# IN.net
KiCad netlist of a schematic drawn in Altium Designer
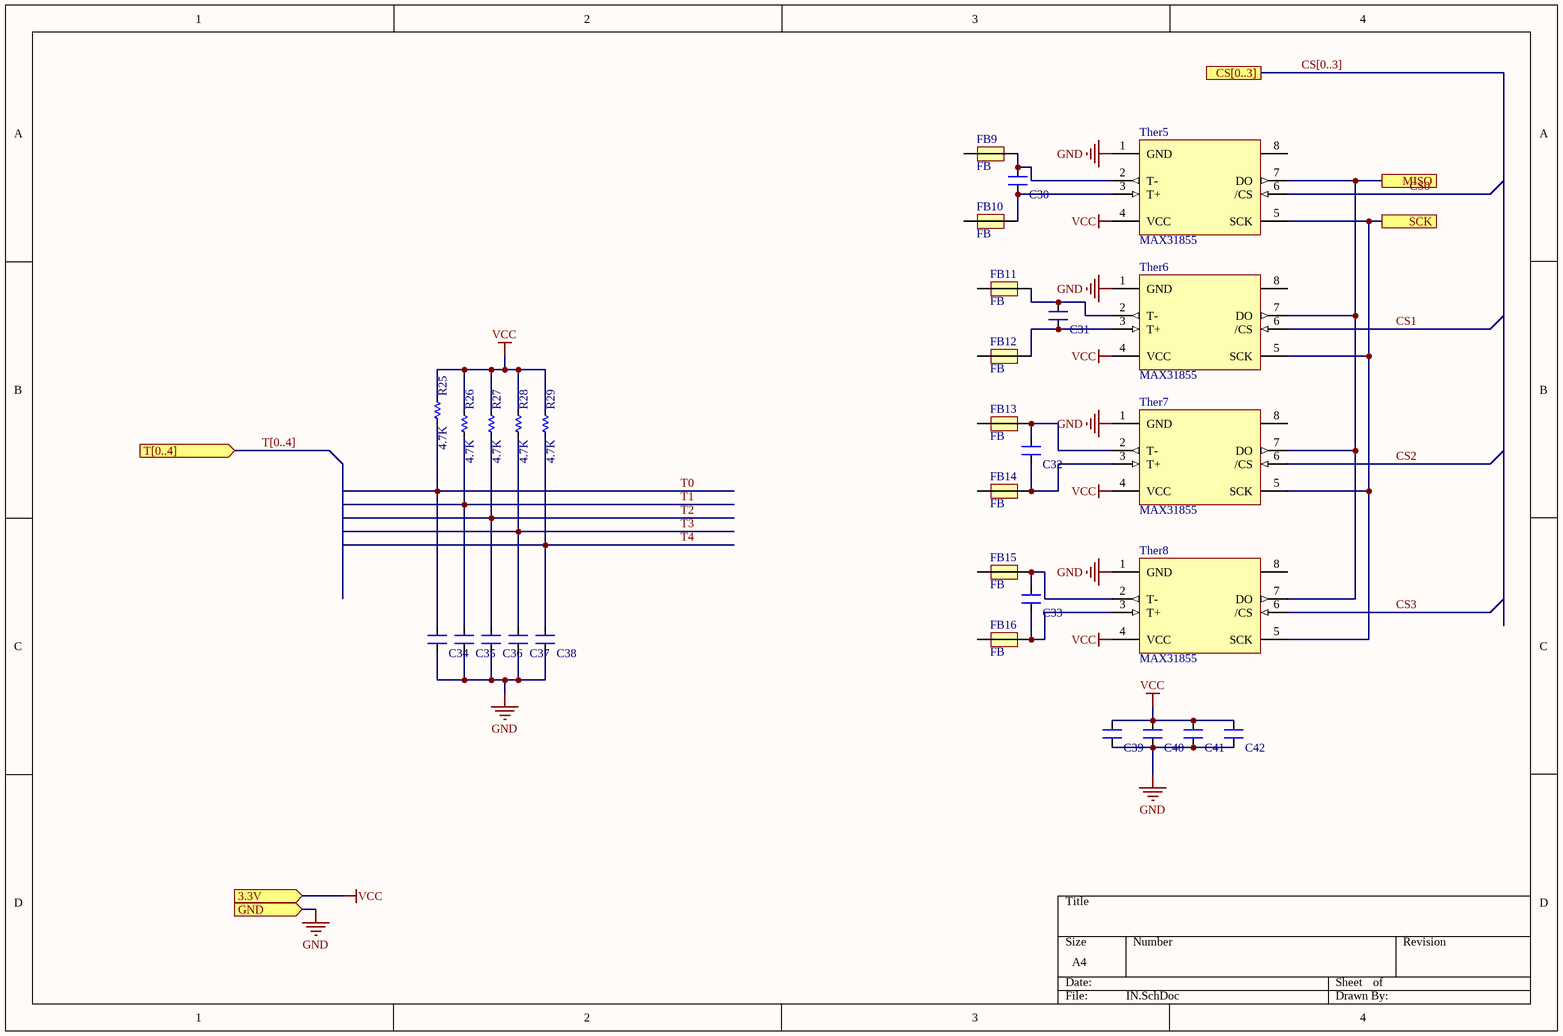
[diagram p0: IN.SchDoc]

(export (version "E")
  (design (tool "Eeschema 10.0.6"))
  (components
    (comp (ref "C30") (value "10nF") (footprint "CN-SMD-0603_big") (libsource (lib "nhan") (part "CN")))
    (comp (ref "C31") (value "10nF") (footprint "CN-SMD-0603_big") (libsource (lib "nhan") (part "CN")))
    (comp (ref "C32") (value "10nF") (footprint "CN-SMD-0603_big") (libsource (lib "nhan") (part "CN")))
    (comp (ref "C33") (value "10nF") (footprint "CN-SMD-0603_big") (libsource (lib "nhan") (part "CN")))
    (comp (ref "C34") (value "10uF") (footprint "CN-SMD-0603_big") (libsource (lib "nhan") (part "CN")))
    (comp (ref "C35") (value "10uF") (footprint "CN-SMD-0603_big") (libsource (lib "nhan") (part "CN")))
    (comp (ref "C36") (value "10uF") (footprint "CN-SMD-0603_big") (libsource (lib "nhan") (part "CN")))
    (comp (ref "C37") (value "10uF") (footprint "CN-SMD-0603_big") (libsource (lib "nhan") (part "CN")))
    (comp (ref "C38") (value "10uF") (footprint "CN-SMD-0603_big") (libsource (lib "nhan") (part "CN")))
    (comp (ref "C39") (value "10nF") (footprint "CN-SMD-0603_big") (libsource (lib "nhan") (part "CN")))
    (comp (ref "C40") (value "10nF") (footprint "CN-SMD-0603_big") (libsource (lib "nhan") (part "CN")))
    (comp (ref "C41") (value "10nF") (footprint "CN-SMD-0603_big") (libsource (lib "nhan") (part "CN")))
    (comp (ref "C42") (value "10nF") (footprint "CN-SMD-0603_big") (libsource (lib "nhan") (part "CN")))
    (comp (ref "FB9") (value "FB") (footprint "Capacitor_805") (libsource (lib "nhan") (part "FB")))
    (comp (ref "FB10") (value "FB") (footprint "Capacitor_805") (libsource (lib "nhan") (part "FB")))
    (comp (ref "FB11") (value "FB") (footprint "Capacitor_805") (libsource (lib "nhan") (part "FB")))
    (comp (ref "FB12") (value "FB") (footprint "Capacitor_805") (libsource (lib "nhan") (part "FB")))
    (comp (ref "FB13") (value "FB") (footprint "Capacitor_805") (libsource (lib "nhan") (part "FB")))
    (comp (ref "FB14") (value "FB") (footprint "Capacitor_805") (libsource (lib "nhan") (part "FB")))
    (comp (ref "FB15") (value "FB") (footprint "Capacitor_805") (libsource (lib "nhan") (part "FB")))
    (comp (ref "FB16") (value "FB") (footprint "Capacitor_805") (libsource (lib "nhan") (part "FB")))
    (comp (ref "R25") (value "4.7K") (footprint "RES-SMD-0603_BIG") (libsource (lib "nhan") (part "R")))
    (comp (ref "R26") (value "4.7K") (footprint "RES-SMD-0603_BIG") (libsource (lib "nhan") (part "R")))
    (comp (ref "R27") (value "4.7K") (footprint "RES-SMD-0603_BIG") (libsource (lib "nhan") (part "R")))
    (comp (ref "R28") (value "4.7K") (footprint "RES-SMD-0603_BIG") (libsource (lib "nhan") (part "R")))
    (comp (ref "R29") (value "4.7K") (footprint "RES-SMD-0603_BIG") (libsource (lib "nhan") (part "R")))
    (comp (ref "Ther5") (value "MAX31855") (footprint "SO8") (libsource (lib "nhan") (part "MAX31855")))
    (comp (ref "Ther6") (value "MAX31855") (footprint "SO8") (libsource (lib "nhan") (part "MAX31855")))
    (comp (ref "Ther7") (value "MAX31855") (footprint "SO8") (libsource (lib "nhan") (part "MAX31855")))
    (comp (ref "Ther8") (value "MAX31855") (footprint "SO8") (libsource (lib "nhan") (part "MAX31855")))
  )
  (nets
    (net (code "1") (name "/CS0") (class "Default")
      (node (ref "Ther5") (pin "6") (pinfunction "/CS_6") (pintype "input"))
    )
    (net (code "2") (name "/CS1") (class "Default")
      (node (ref "Ther6") (pin "6") (pinfunction "/CS_6") (pintype "input"))
    )
    (net (code "3") (name "/CS2") (class "Default")
      (node (ref "Ther7") (pin "6") (pinfunction "/CS_6") (pintype "input"))
    )
    (net (code "4") (name "/CS3") (class "Default")
      (node (ref "Ther8") (pin "6") (pinfunction "/CS_6") (pintype "input"))
    )
    (net (code "6") (name "/MISO") (class "Default")
      (node (ref "Ther5") (pin "7") (pinfunction "DO_7") (pintype "output"))
      (node (ref "Ther6") (pin "7") (pinfunction "DO_7") (pintype "output"))
      (node (ref "Ther7") (pin "7") (pinfunction "DO_7") (pintype "output"))
      (node (ref "Ther8") (pin "7") (pinfunction "DO_7") (pintype "output"))
    )
    (net (code "7") (name "/SCK") (class "Default")
      (node (ref "Ther5") (pin "5") (pinfunction "SCK_5") (pintype "passive"))
      (node (ref "Ther6") (pin "5") (pinfunction "SCK_5") (pintype "passive"))
      (node (ref "Ther7") (pin "5") (pinfunction "SCK_5") (pintype "passive"))
      (node (ref "Ther8") (pin "5") (pinfunction "SCK_5") (pintype "passive"))
    )
    (net (code "8") (name "/T0") (class "Default")
      (node (ref "C34") (pin "2") (pinfunction "2_2") (pintype "passive"))
      (node (ref "R25") (pin "2") (pinfunction "2_2") (pintype "passive"))
    )
    (net (code "9") (name "/T1") (class "Default")
      (node (ref "C35") (pin "2") (pinfunction "2_2") (pintype "passive"))
      (node (ref "R26") (pin "2") (pinfunction "2_2") (pintype "passive"))
    )
    (net (code "10") (name "/T2") (class "Default")
      (node (ref "C36") (pin "2") (pinfunction "2_2") (pintype "passive"))
      (node (ref "R27") (pin "2") (pinfunction "2_2") (pintype "passive"))
    )
    (net (code "11") (name "/T3") (class "Default")
      (node (ref "C37") (pin "2") (pinfunction "2_2") (pintype "passive"))
      (node (ref "R28") (pin "2") (pinfunction "2_2") (pintype "passive"))
    )
    (net (code "12") (name "/T4") (class "Default")
      (node (ref "C38") (pin "2") (pinfunction "2_2") (pintype "passive"))
      (node (ref "R29") (pin "2") (pinfunction "2_2") (pintype "passive"))
    )
    (net (code "14") (name "GND") (class "Default")
      (node (ref "C34") (pin "1") (pinfunction "1_1") (pintype "passive"))
      (node (ref "C35") (pin "1") (pinfunction "1_1") (pintype "passive"))
      (node (ref "C36") (pin "1") (pinfunction "1_1") (pintype "passive"))
      (node (ref "C37") (pin "1") (pinfunction "1_1") (pintype "passive"))
      (node (ref "C38") (pin "1") (pinfunction "1_1") (pintype "passive"))
      (node (ref "C39") (pin "1") (pinfunction "1_1") (pintype "passive"))
      (node (ref "C40") (pin "1") (pinfunction "1_1") (pintype "passive"))
      (node (ref "C41") (pin "1") (pinfunction "1_1") (pintype "passive"))
      (node (ref "C42") (pin "1") (pinfunction "1_1") (pintype "passive"))
      (node (ref "Ther5") (pin "1") (pinfunction "GND_1") (pintype "passive"))
      (node (ref "Ther6") (pin "1") (pinfunction "GND_1") (pintype "passive"))
      (node (ref "Ther7") (pin "1") (pinfunction "GND_1") (pintype "passive"))
      (node (ref "Ther8") (pin "1") (pinfunction "GND_1") (pintype "passive"))
    )
    (net (code "15") (name "Net-(Ther5-T+)") (class "Default")
      (node (ref "C30") (pin "1") (pinfunction "1_1") (pintype "passive"))
      (node (ref "FB10") (pin "2") (pinfunction "2_2") (pintype "passive"))
      (node (ref "Ther5") (pin "3") (pinfunction "T+_3") (pintype "input"))
    )
    (net (code "16") (name "Net-(Ther5-T-)") (class "Default")
      (node (ref "C30") (pin "2") (pinfunction "2_2") (pintype "passive"))
      (node (ref "FB9") (pin "2") (pinfunction "2_2") (pintype "passive"))
      (node (ref "Ther5") (pin "2") (pinfunction "T-_2") (pintype "output"))
    )
    (net (code "17") (name "Net-(Ther6-T+)") (class "Default")
      (node (ref "C31") (pin "1") (pinfunction "1_1") (pintype "passive"))
      (node (ref "FB12") (pin "2") (pinfunction "2_2") (pintype "passive"))
      (node (ref "Ther6") (pin "3") (pinfunction "T+_3") (pintype "input"))
    )
    (net (code "18") (name "Net-(Ther6-T-)") (class "Default")
      (node (ref "C31") (pin "2") (pinfunction "2_2") (pintype "passive"))
      (node (ref "FB11") (pin "2") (pinfunction "2_2") (pintype "passive"))
      (node (ref "Ther6") (pin "2") (pinfunction "T-_2") (pintype "output"))
    )
    (net (code "19") (name "Net-(Ther7-T+)") (class "Default")
      (node (ref "C32") (pin "1") (pinfunction "1_1") (pintype "passive"))
      (node (ref "FB14") (pin "2") (pinfunction "2_2") (pintype "passive"))
      (node (ref "Ther7") (pin "3") (pinfunction "T+_3") (pintype "input"))
    )
    (net (code "20") (name "Net-(Ther7-T-)") (class "Default")
      (node (ref "C32") (pin "2") (pinfunction "2_2") (pintype "passive"))
      (node (ref "FB13") (pin "2") (pinfunction "2_2") (pintype "passive"))
      (node (ref "Ther7") (pin "2") (pinfunction "T-_2") (pintype "output"))
    )
    (net (code "21") (name "Net-(Ther8-T+)") (class "Default")
      (node (ref "C33") (pin "1") (pinfunction "1_1") (pintype "passive"))
      (node (ref "FB16") (pin "2") (pinfunction "2_2") (pintype "passive"))
      (node (ref "Ther8") (pin "3") (pinfunction "T+_3") (pintype "input"))
    )
    (net (code "22") (name "Net-(Ther8-T-)") (class "Default")
      (node (ref "C33") (pin "2") (pinfunction "2_2") (pintype "passive"))
      (node (ref "FB15") (pin "2") (pinfunction "2_2") (pintype "passive"))
      (node (ref "Ther8") (pin "2") (pinfunction "T-_2") (pintype "output"))
    )
    (net (code "23") (name "VCC") (class "Default")
      (node (ref "C39") (pin "2") (pinfunction "2_2") (pintype "passive"))
      (node (ref "C40") (pin "2") (pinfunction "2_2") (pintype "passive"))
      (node (ref "C41") (pin "2") (pinfunction "2_2") (pintype "passive"))
      (node (ref "C42") (pin "2") (pinfunction "2_2") (pintype "passive"))
      (node (ref "R25") (pin "1") (pinfunction "1_1") (pintype "passive"))
      (node (ref "R26") (pin "1") (pinfunction "1_1") (pintype "passive"))
      (node (ref "R27") (pin "1") (pinfunction "1_1") (pintype "passive"))
      (node (ref "R28") (pin "1") (pinfunction "1_1") (pintype "passive"))
      (node (ref "R29") (pin "1") (pinfunction "1_1") (pintype "passive"))
      (node (ref "Ther5") (pin "4") (pinfunction "VCC_4") (pintype "passive"))
      (node (ref "Ther6") (pin "4") (pinfunction "VCC_4") (pintype "passive"))
      (node (ref "Ther7") (pin "4") (pinfunction "VCC_4") (pintype "passive"))
      (node (ref "Ther8") (pin "4") (pinfunction "VCC_4") (pintype "passive"))
    )
    (net (code "24") (name "unconnected-(FB9-Pad1)") (class "Default")
      (node (ref "FB9") (pin "1") (pinfunction "1_1") (pintype "passive"))
    )
    (net (code "25") (name "unconnected-(FB10-Pad1)") (class "Default")
      (node (ref "FB10") (pin "1") (pinfunction "1_1") (pintype "passive"))
    )
    (net (code "26") (name "unconnected-(FB11-Pad1)") (class "Default")
      (node (ref "FB11") (pin "1") (pinfunction "1_1") (pintype "passive"))
    )
    (net (code "27") (name "unconnected-(FB12-Pad1)") (class "Default")
      (node (ref "FB12") (pin "1") (pinfunction "1_1") (pintype "passive"))
    )
    (net (code "28") (name "unconnected-(FB13-Pad1)") (class "Default")
      (node (ref "FB13") (pin "1") (pinfunction "1_1") (pintype "passive"))
    )
    (net (code "29") (name "unconnected-(FB14-Pad1)") (class "Default")
      (node (ref "FB14") (pin "1") (pinfunction "1_1") (pintype "passive"))
    )
    (net (code "30") (name "unconnected-(FB15-Pad1)") (class "Default")
      (node (ref "FB15") (pin "1") (pinfunction "1_1") (pintype "passive"))
    )
    (net (code "31") (name "unconnected-(FB16-Pad1)") (class "Default")
      (node (ref "FB16") (pin "1") (pinfunction "1_1") (pintype "passive"))
    )
    (net (code "32") (name "unconnected-(Ther5-Pad8)") (class "Default")
      (node (ref "Ther5") (pin "8") (pintype "passive"))
    )
    (net (code "33") (name "unconnected-(Ther6-Pad8)") (class "Default")
      (node (ref "Ther6") (pin "8") (pintype "passive"))
    )
    (net (code "34") (name "unconnected-(Ther7-Pad8)") (class "Default")
      (node (ref "Ther7") (pin "8") (pintype "passive"))
    )
    (net (code "35") (name "unconnected-(Ther8-Pad8)") (class "Default")
      (node (ref "Ther8") (pin "8") (pintype "passive"))
    )
  )
)
